# Radio.net
KiCad netlist of a schematic drawn in EAGLE
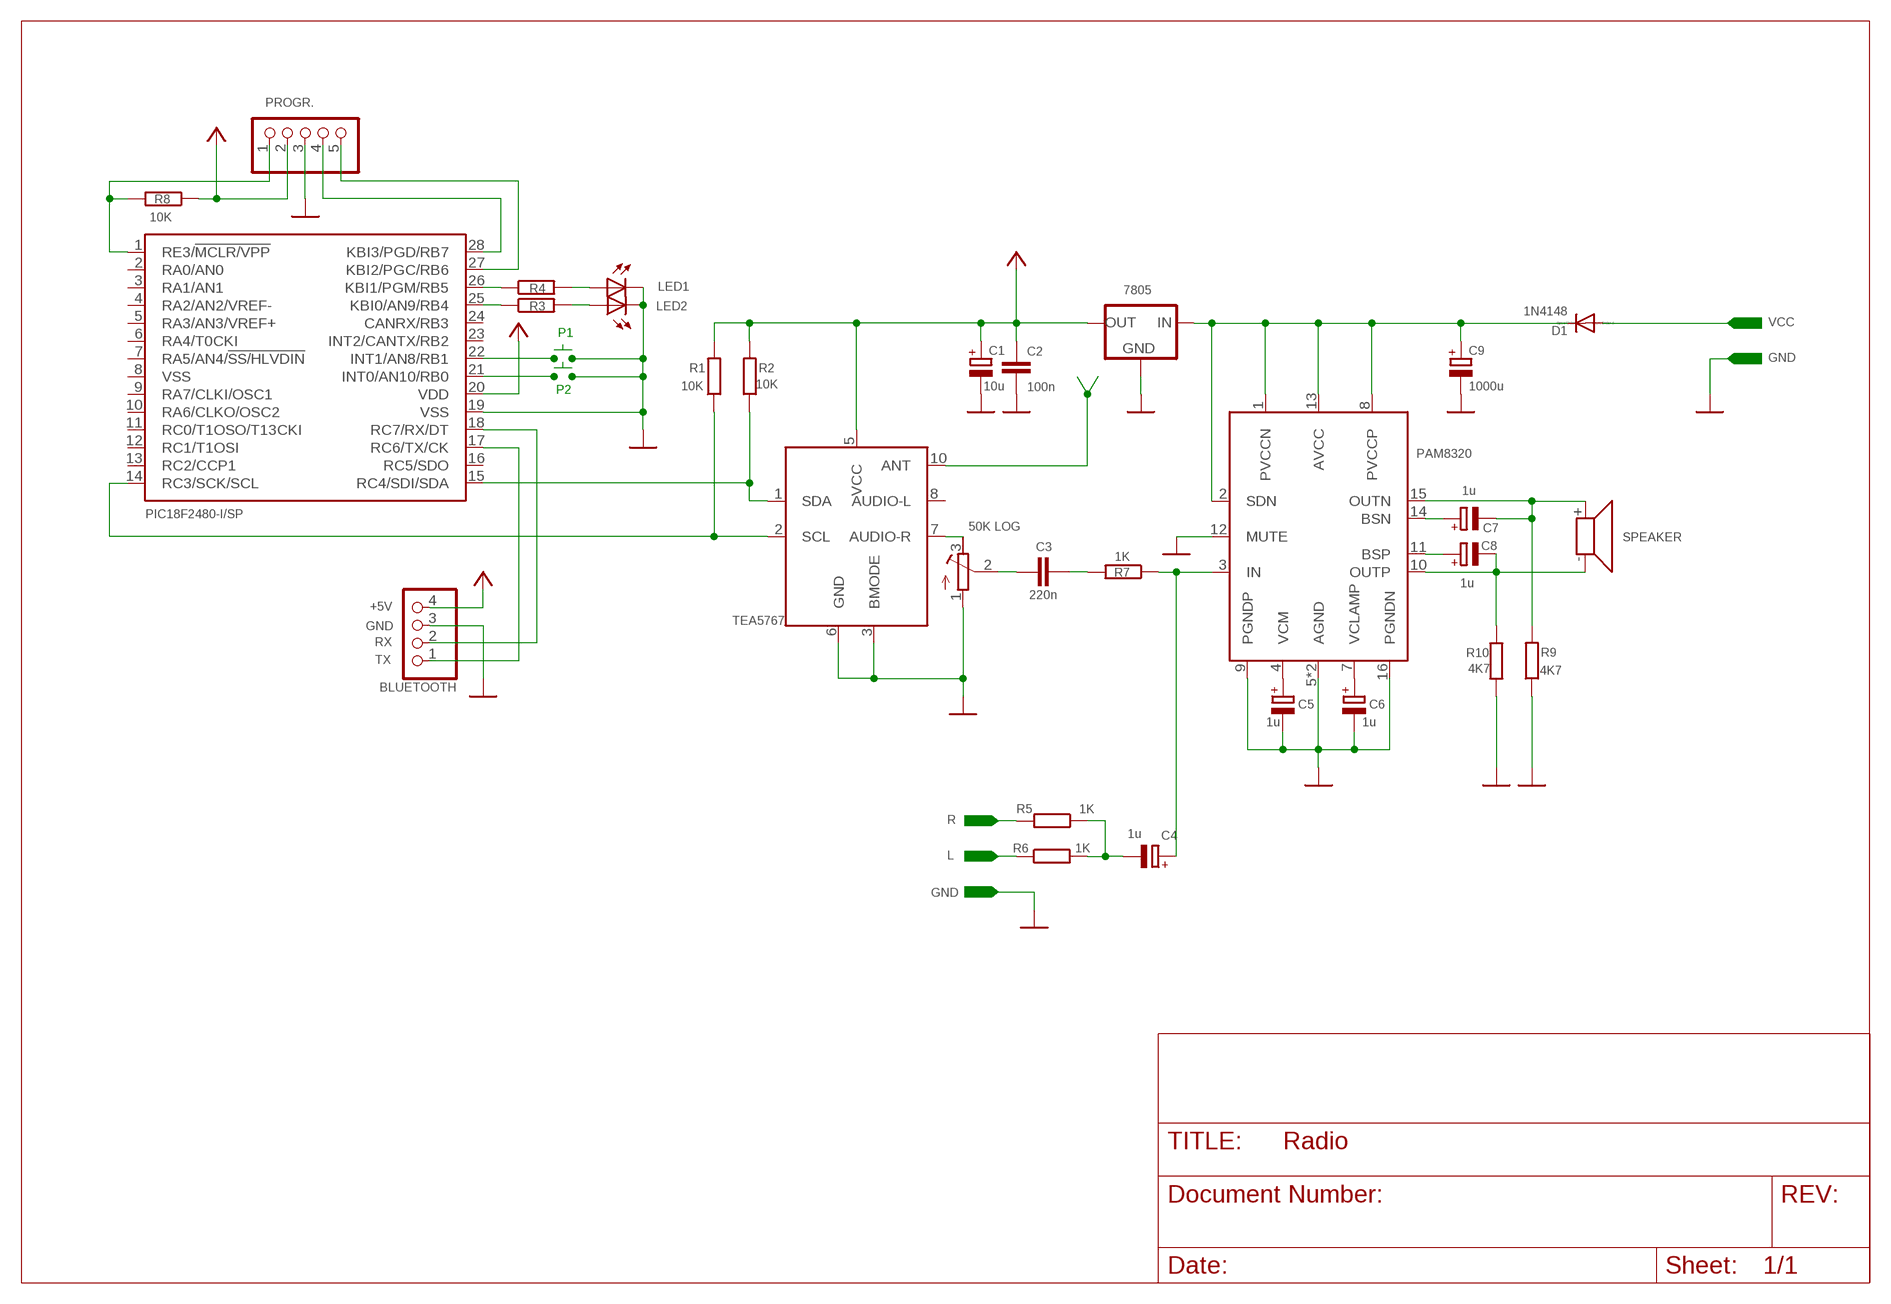
[diagram p0: schematic, sheet 1]

(export (version "E")
  (design (tool "Eeschema 10.0.6"))
  (components
    (comp (ref "7805")
      (value "78XXL")
      (footprint "eagle-import:78XXL")
      (libsource (lib "eagle-import") (part "78XXL"))
    )
    (comp (ref "BLUETOOTH")
      (value "PINHD-1X4")
      (footprint "eagle-import:1X04")
      (libsource (lib "eagle-import") (part "PINHD-1X4"))
    )
    (comp (ref "C1")
      (value "10u")
      (footprint "eagle-import:E2,5-6E")
      (libsource (lib "eagle-import") (part "CPOL-EUE2,5-6E"))
    )
    (comp (ref "C2")
      (value "100n")
      (footprint "eagle-import:C050-024X044")
      (libsource (lib "eagle-import") (part "C-EU050-024X044"))
    )
    (comp (ref "C3")
      (value "220n")
      (footprint "eagle-import:C050-024X044")
      (libsource (lib "eagle-import") (part "C-EU050-024X044"))
    )
    (comp (ref "C4")
      (value "1u")
      (footprint "eagle-import:E2,5-6E")
      (libsource (lib "eagle-import") (part "CPOL-EUE2,5-6E"))
    )
    (comp (ref "C5")
      (value "1u")
      (footprint "eagle-import:E2,5-6E")
      (libsource (lib "eagle-import") (part "CPOL-EUE2,5-6E"))
    )
    (comp (ref "C6")
      (value "1u")
      (footprint "eagle-import:E2,5-6E")
      (libsource (lib "eagle-import") (part "CPOL-EUE2,5-6E"))
    )
    (comp (ref "C7")
      (value "1u")
      (footprint "eagle-import:E2,5-6E")
      (libsource (lib "eagle-import") (part "CPOL-EUE2,5-6E"))
    )
    (comp (ref "C8")
      (value "1u")
      (footprint "eagle-import:E2,5-6E")
      (libsource (lib "eagle-import") (part "CPOL-EUE2,5-6E"))
    )
    (comp (ref "C9")
      (value "1000u")
      (footprint "eagle-import:E5-13")
      (libsource (lib "eagle-import") (part "CPOL-EUE5-13"))
    )
    (comp (ref "D1")
      (value "1N4148")
      (footprint "eagle-import:DO35-7")
      (libsource (lib "eagle-import") (part "1N4148DO35-7"))
    )
    (comp (ref "IC2")
      (value "PIC18F2480-I/SP")
      (footprint "eagle-import:DIL28-3")
      (fields (field (name "MF") "MICROCHIP"))
      (libsource (lib "eagle-import") (part "PIC18F280-I/SP4"))
    )
    (comp (ref "LED1")
      (value "LED5MM")
      (footprint "eagle-import:LED5MM")
      (libsource (lib "eagle-import") (part "LED5MM"))
    )
    (comp (ref "LED2")
      (value "LED5MM")
      (footprint "eagle-import:LED5MM")
      (libsource (lib "eagle-import") (part "LED5MM"))
    )
    (comp (ref "PAM8320")
      (value "PAM8320")
      (footprint "eagle-import:DIL16")
      (libsource (lib "eagle-import") (part "PAM8320"))
    )
    (comp (ref "POT1")
      (value "50K LOG")
      (footprint "eagle-import:RTRIM64X")
      (libsource (lib "eagle-import") (part "R-TRIMM64X"))
    )
    (comp (ref "PROGR.")
      (value "PINHD-1X55X2MM")
      (footprint "eagle-import:1_05X2MM")
      (libsource (lib "eagle-import") (part "PINHD-1X55X2MM"))
    )
    (comp (ref "R1")
      (value "10K")
      (footprint "eagle-import:0207_10")
      (libsource (lib "eagle-import") (part "R-EU_0207/10"))
    )
    (comp (ref "R2")
      (value "10K")
      (footprint "eagle-import:0207_10")
      (libsource (lib "eagle-import") (part "R-EU_0207/10"))
    )
    (comp (ref "R3")
      (value "2x330")
      (footprint "eagle-import:0207_10")
      (libsource (lib "eagle-import") (part "R-EU_0207/10"))
    )
    (comp (ref "R4")
      (value "330")
      (footprint "eagle-import:0207_10")
      (libsource (lib "eagle-import") (part "R-EU_0207/10"))
    )
    (comp (ref "R5")
      (value "1K")
      (footprint "eagle-import:0207_10")
      (libsource (lib "eagle-import") (part "R-EU_0207/10"))
    )
    (comp (ref "R6")
      (value "1K")
      (footprint "eagle-import:0207_10")
      (libsource (lib "eagle-import") (part "R-EU_0207/10"))
    )
    (comp (ref "R7")
      (value "1K")
      (footprint "eagle-import:0207_10")
      (libsource (lib "eagle-import") (part "R-EU_0207/10"))
    )
    (comp (ref "R8")
      (value "10K")
      (footprint "eagle-import:0207_10")
      (libsource (lib "eagle-import") (part "R-EU_0207/10"))
    )
    (comp (ref "R9")
      (value "4K7")
      (footprint "eagle-import:0207_10")
      (libsource (lib "eagle-import") (part "R-EU_0207/10"))
    )
    (comp (ref "R10")
      (value "4K7")
      (footprint "eagle-import:0207_10")
      (libsource (lib "eagle-import") (part "R-EU_0207/10"))
    )
    (comp (ref "SPEAKER")
      (value "SMS-1308MS-2-R")
      (footprint "eagle-import:SMS-1308MS-2-R")
      (libsource (lib "eagle-import") (part "SMS-1308MS-2-R"))
    )
    (comp (ref "TEA5767")
      (value "TEA5767")
      (footprint "eagle-import:TEA5767")
      (libsource (lib "eagle-import") (part "TEA5767"))
    )
  )
  (nets
    (net (code "1") (name "+5V") (class "Default")
      (node (ref "7805") (pin "OUT") (pinfunction "OUT_OUT") (pintype "passive"))
      (node (ref "BLUETOOTH") (pin "4") (pinfunction "4_4") (pintype "passive"))
      (node (ref "C1") (pin "+") (pinfunction "+_+") (pintype "passive"))
      (node (ref "C2") (pin "1") (pinfunction "1_1") (pintype "passive"))
      (node (ref "IC2") (pin "20") (pinfunction "VDD_20") (pintype "power_in"))
      (node (ref "PROGR.") (pin "2") (pinfunction "2_2") (pintype "passive"))
      (node (ref "R1") (pin "2") (pinfunction "2_2") (pintype "passive"))
      (node (ref "R2") (pin "2") (pinfunction "2_2") (pintype "passive"))
      (node (ref "R8") (pin "1") (pinfunction "1_1") (pintype "passive"))
      (node (ref "TEA5767") (pin "5") (pinfunction "VCC_5") (pintype "bidirectional"))
    )
    (net (code "2") (name "/N$20") (class "Default")
      (node (ref "IC2") (pin "21") (pinfunction "INT0/AN10/RB0_21") (pintype "bidirectional"))
      (node (ref "IC2") (pin "22") (pinfunction "INT1/AN8/RB1_22") (pintype "bidirectional"))
    )
    (net (code "4") (name "/RX") (class "Default")
      (node (ref "BLUETOOTH") (pin "2") (pinfunction "2_2") (pintype "passive"))
      (node (ref "IC2") (pin "18") (pinfunction "RC7/RX/DT_18") (pintype "bidirectional"))
    )
    (net (code "5") (name "/TX") (class "Default")
      (node (ref "BLUETOOTH") (pin "1") (pinfunction "1_1") (pintype "passive"))
      (node (ref "IC2") (pin "17") (pinfunction "RC6/TX/CK_17") (pintype "bidirectional"))
    )
    (net (code "6") (name "/VSS") (class "Default")
      (node (ref "IC2") (pin "8") (pinfunction "VSS_8") (pintype "power_in"))
    )
    (net (code "7") (name "GND") (class "Default")
      (node (ref "7805") (pin "GND") (pinfunction "GND_GND") (pintype "input"))
      (node (ref "BLUETOOTH") (pin "3") (pinfunction "3_3") (pintype "passive"))
      (node (ref "C1") (pin "-") (pinfunction "-_-") (pintype "passive"))
      (node (ref "C2") (pin "2") (pinfunction "2_2") (pintype "passive"))
      (node (ref "C5") (pin "-") (pinfunction "-_-") (pintype "passive"))
      (node (ref "C6") (pin "-") (pinfunction "-_-") (pintype "passive"))
      (node (ref "C9") (pin "-") (pinfunction "-_-") (pintype "passive"))
      (node (ref "IC2") (pin "19") (pinfunction "VSS_19") (pintype "power_in"))
      (node (ref "LED1") (pin "K") (pinfunction "C_K") (pintype "passive"))
      (node (ref "LED2") (pin "K") (pinfunction "C_K") (pintype "passive"))
      (node (ref "PAM8320") (pin "12") (pinfunction "MUTE_12") (pintype "bidirectional"))
      (node (ref "PAM8320") (pin "16") (pinfunction "PGNDN_16") (pintype "bidirectional"))
      (node (ref "PAM8320") (pin "5") (pinfunction "AGND_5") (pintype "bidirectional"))
      (node (ref "PAM8320") (pin "6") (pinfunction "AGND_6") (pintype "bidirectional"))
      (node (ref "PAM8320") (pin "9") (pinfunction "PGNDP_9") (pintype "bidirectional"))
      (node (ref "POT1") (pin "1") (pinfunction "A_1") (pintype "passive"))
      (node (ref "PROGR.") (pin "3") (pinfunction "3_3") (pintype "passive"))
      (node (ref "R10") (pin "2") (pinfunction "2_2") (pintype "passive"))
      (node (ref "R9") (pin "1") (pinfunction "1_1") (pintype "passive"))
      (node (ref "TEA5767") (pin "3") (pinfunction "BMODE_3") (pintype "bidirectional"))
      (node (ref "TEA5767") (pin "6") (pinfunction "GND_6") (pintype "bidirectional"))
    )
    (net (code "8") (name "Net-(C3-Pad2)") (class "Default")
      (node (ref "C3") (pin "2") (pinfunction "2_2") (pintype "passive"))
      (node (ref "R7") (pin "2") (pinfunction "2_2") (pintype "passive"))
    )
    (net (code "9") (name "Net-(C4-Pad-)") (class "Default")
      (node (ref "C4") (pin "-") (pinfunction "-_-") (pintype "passive"))
      (node (ref "R5") (pin "1") (pinfunction "1_1") (pintype "passive"))
      (node (ref "R6") (pin "2") (pinfunction "2_2") (pintype "passive"))
    )
    (net (code "10") (name "Net-(IC2-KBI0{slash}AN9{slash}RB4)") (class "Default")
      (node (ref "IC2") (pin "25") (pinfunction "KBI0/AN9/RB4_25") (pintype "bidirectional"))
      (node (ref "R3") (pin "1") (pinfunction "1_1") (pintype "passive"))
    )
    (net (code "11") (name "Net-(IC2-KBI1{slash}PGM{slash}RB5)") (class "Default")
      (node (ref "IC2") (pin "26") (pinfunction "KBI1/PGM/RB5_26") (pintype "bidirectional"))
      (node (ref "R4") (pin "1") (pinfunction "1_1") (pintype "passive"))
    )
    (net (code "12") (name "Net-(IC2-KBI2{slash}PGC{slash}RB6)") (class "Default")
      (node (ref "IC2") (pin "27") (pinfunction "KBI2/PGC/RB6_27") (pintype "bidirectional"))
      (node (ref "PROGR.") (pin "5") (pinfunction "5_5") (pintype "passive"))
    )
    (net (code "13") (name "Net-(IC2-KBI3{slash}PGD{slash}RB7)") (class "Default")
      (node (ref "IC2") (pin "28") (pinfunction "KBI3/PGD/RB7_28") (pintype "bidirectional"))
      (node (ref "PROGR.") (pin "4") (pinfunction "4_4") (pintype "passive"))
    )
    (net (code "14") (name "Net-(IC2-RC3{slash}SCK{slash}SCL)") (class "Default")
      (node (ref "IC2") (pin "14") (pinfunction "RC3/SCK/SCL_14") (pintype "bidirectional"))
      (node (ref "R1") (pin "1") (pinfunction "1_1") (pintype "passive"))
      (node (ref "TEA5767") (pin "2") (pinfunction "SCL_2") (pintype "bidirectional"))
    )
    (net (code "15") (name "Net-(IC2-RC4{slash}SDI{slash}SDA)") (class "Default")
      (node (ref "IC2") (pin "15") (pinfunction "RC4/SDI/SDA_15") (pintype "bidirectional"))
      (node (ref "R2") (pin "1") (pinfunction "1_1") (pintype "passive"))
      (node (ref "TEA5767") (pin "1") (pinfunction "SDA_1") (pintype "bidirectional"))
    )
    (net (code "16") (name "Net-(IC2-RE3{slash}~{MCLR{slash}VPP})") (class "Default")
      (node (ref "IC2") (pin "1") (pinfunction "RE3/~{MCLR/VPP}_1") (pintype "input"))
      (node (ref "PROGR.") (pin "1") (pinfunction "1_1") (pintype "passive"))
      (node (ref "R8") (pin "2") (pinfunction "2_2") (pintype "passive"))
    )
    (net (code "17") (name "Net-(LED1-PadA)") (class "Default")
      (node (ref "LED1") (pin "A") (pinfunction "A_A") (pintype "passive"))
      (node (ref "R4") (pin "2") (pinfunction "2_2") (pintype "passive"))
    )
    (net (code "18") (name "Net-(LED2-PadA)") (class "Default")
      (node (ref "LED2") (pin "A") (pinfunction "A_A") (pintype "passive"))
      (node (ref "R3") (pin "2") (pinfunction "2_2") (pintype "passive"))
    )
    (net (code "19") (name "Net-(PAM8320-AVCC)") (class "Default")
      (node (ref "7805") (pin "IN") (pinfunction "IN_IN") (pintype "input"))
      (node (ref "C9") (pin "+") (pinfunction "+_+") (pintype "passive"))
      (node (ref "D1") (pin "C") (pinfunction "C_C") (pintype "passive"))
      (node (ref "PAM8320") (pin "1") (pinfunction "PVCCN_1") (pintype "bidirectional"))
      (node (ref "PAM8320") (pin "13") (pinfunction "AVCC_13") (pintype "bidirectional"))
      (node (ref "PAM8320") (pin "2") (pinfunction "SDN_2") (pintype "bidirectional"))
      (node (ref "PAM8320") (pin "8") (pinfunction "PVCCP_8") (pintype "bidirectional"))
    )
    (net (code "20") (name "Net-(PAM8320-BSN)") (class "Default")
      (node (ref "C7") (pin "+") (pinfunction "+_+") (pintype "passive"))
      (node (ref "PAM8320") (pin "14") (pinfunction "BSN_14") (pintype "bidirectional"))
    )
    (net (code "21") (name "Net-(PAM8320-BSP)") (class "Default")
      (node (ref "C8") (pin "+") (pinfunction "+_+") (pintype "passive"))
      (node (ref "PAM8320") (pin "11") (pinfunction "BSP_11") (pintype "bidirectional"))
    )
    (net (code "22") (name "Net-(PAM8320-IN)") (class "Default")
      (node (ref "C4") (pin "+") (pinfunction "+_+") (pintype "passive"))
      (node (ref "PAM8320") (pin "3") (pinfunction "IN_3") (pintype "bidirectional"))
      (node (ref "R7") (pin "1") (pinfunction "1_1") (pintype "passive"))
    )
    (net (code "23") (name "Net-(PAM8320-OUTN)") (class "Default")
      (node (ref "C7") (pin "-") (pinfunction "-_-") (pintype "passive"))
      (node (ref "PAM8320") (pin "15") (pinfunction "OUTN_15") (pintype "bidirectional"))
      (node (ref "R9") (pin "2") (pinfunction "2_2") (pintype "passive"))
      (node (ref "SPEAKER") (pin "+") (pinfunction "1_+") (pintype "passive"))
    )
    (net (code "24") (name "Net-(PAM8320-OUTP)") (class "Default")
      (node (ref "C8") (pin "-") (pinfunction "-_-") (pintype "passive"))
      (node (ref "PAM8320") (pin "10") (pinfunction "OUTP_10") (pintype "bidirectional"))
      (node (ref "R10") (pin "1") (pinfunction "1_1") (pintype "passive"))
      (node (ref "SPEAKER") (pin "-") (pinfunction "2_-") (pintype "passive"))
    )
    (net (code "25") (name "Net-(PAM8320-VCLAMP)") (class "Default")
      (node (ref "C6") (pin "+") (pinfunction "+_+") (pintype "passive"))
      (node (ref "PAM8320") (pin "7") (pinfunction "VCLAMP_7") (pintype "bidirectional"))
    )
    (net (code "26") (name "Net-(PAM8320-VCM)") (class "Default")
      (node (ref "C5") (pin "+") (pinfunction "+_+") (pintype "passive"))
      (node (ref "PAM8320") (pin "4") (pinfunction "VCM_4") (pintype "bidirectional"))
    )
    (net (code "27") (name "Net-(POT1-E)") (class "Default")
      (node (ref "POT1") (pin "3") (pinfunction "E_3") (pintype "passive"))
      (node (ref "TEA5767") (pin "7") (pinfunction "AUDIO-R_7") (pintype "bidirectional"))
    )
    (net (code "28") (name "Net-(POT1-S)") (class "Default")
      (node (ref "C3") (pin "1") (pinfunction "1_1") (pintype "passive"))
      (node (ref "POT1") (pin "2") (pinfunction "S_2") (pintype "passive"))
    )
    (net (code "29") (name "unconnected-(D1-PadA)") (class "Default")
      (node (ref "D1") (pin "A") (pinfunction "A_A") (pintype "passive"))
    )
    (net (code "30") (name "unconnected-(IC2-CANRX{slash}RB3-Pad24)") (class "Default")
      (node (ref "IC2") (pin "24") (pinfunction "CANRX/RB3_24") (pintype "bidirectional"))
    )
    (net (code "31") (name "unconnected-(IC2-INT2{slash}CANTX{slash}RB2-Pad23)") (class "Default")
      (node (ref "IC2") (pin "23") (pinfunction "INT2/CANTX/RB2_23") (pintype "bidirectional"))
    )
    (net (code "32") (name "unconnected-(IC2-RA0{slash}AN0-Pad2)") (class "Default")
      (node (ref "IC2") (pin "2") (pinfunction "RA0/AN0_2") (pintype "bidirectional"))
    )
    (net (code "33") (name "unconnected-(IC2-RA1{slash}AN1-Pad3)") (class "Default")
      (node (ref "IC2") (pin "3") (pinfunction "RA1/AN1_3") (pintype "bidirectional"))
    )
    (net (code "34") (name "unconnected-(IC2-RA2{slash}AN2{slash}VREF--Pad4)") (class "Default")
      (node (ref "IC2") (pin "4") (pinfunction "RA2/AN2/VREF-_4") (pintype "bidirectional"))
    )
    (net (code "35") (name "unconnected-(IC2-RA3{slash}AN3{slash}VREF+-Pad5)") (class "Default")
      (node (ref "IC2") (pin "5") (pinfunction "RA3/AN3/VREF+_5") (pintype "bidirectional"))
    )
    (net (code "36") (name "unconnected-(IC2-RA4{slash}T0CKI-Pad6)") (class "Default")
      (node (ref "IC2") (pin "6") (pinfunction "RA4/T0CKI_6") (pintype "bidirectional"))
    )
    (net (code "37") (name "unconnected-(IC2-RA5{slash}AN4{slash}~{SS{slash}HLVDIN}-Pad7)") (class "Default")
      (node (ref "IC2") (pin "7") (pinfunction "RA5/AN4/~{SS/HLVDIN}_7") (pintype "bidirectional"))
    )
    (net (code "38") (name "unconnected-(IC2-RA6{slash}CLKO{slash}OSC2-Pad10)") (class "Default")
      (node (ref "IC2") (pin "10") (pinfunction "RA6/CLKO/OSC2_10") (pintype "output"))
    )
    (net (code "39") (name "unconnected-(IC2-RA7{slash}CLKI{slash}OSC1-Pad9)") (class "Default")
      (node (ref "IC2") (pin "9") (pinfunction "RA7/CLKI/OSC1_9") (pintype "input"))
    )
    (net (code "40") (name "unconnected-(IC2-RC0{slash}T1OSO{slash}T13CKI-Pad11)") (class "Default")
      (node (ref "IC2") (pin "11") (pinfunction "RC0/T1OSO/T13CKI_11") (pintype "bidirectional"))
    )
    (net (code "41") (name "unconnected-(IC2-RC1{slash}T1OSI-Pad12)") (class "Default")
      (node (ref "IC2") (pin "12") (pinfunction "RC1/T1OSI_12") (pintype "bidirectional"))
    )
    (net (code "42") (name "unconnected-(IC2-RC2{slash}CCP1-Pad13)") (class "Default")
      (node (ref "IC2") (pin "13") (pinfunction "RC2/CCP1_13") (pintype "bidirectional"))
    )
    (net (code "43") (name "unconnected-(IC2-RC5{slash}SDO-Pad16)") (class "Default")
      (node (ref "IC2") (pin "16") (pinfunction "RC5/SDO_16") (pintype "bidirectional"))
    )
    (net (code "44") (name "unconnected-(R5-Pad2)") (class "Default")
      (node (ref "R5") (pin "2") (pinfunction "2_2") (pintype "passive"))
    )
    (net (code "45") (name "unconnected-(R6-Pad1)") (class "Default")
      (node (ref "R6") (pin "1") (pinfunction "1_1") (pintype "passive"))
    )
    (net (code "46") (name "unconnected-(TEA5767-ANT-Pad10)") (class "Default")
      (node (ref "TEA5767") (pin "10") (pinfunction "ANT_10") (pintype "bidirectional"))
    )
    (net (code "47") (name "unconnected-(TEA5767-AUDIO-L-Pad8)") (class "Default")
      (node (ref "TEA5767") (pin "8") (pinfunction "AUDIO-L_8") (pintype "bidirectional"))
    )
  )
)
